# Sheet1.net
KiCad netlist of a schematic drawn in Altium Designer
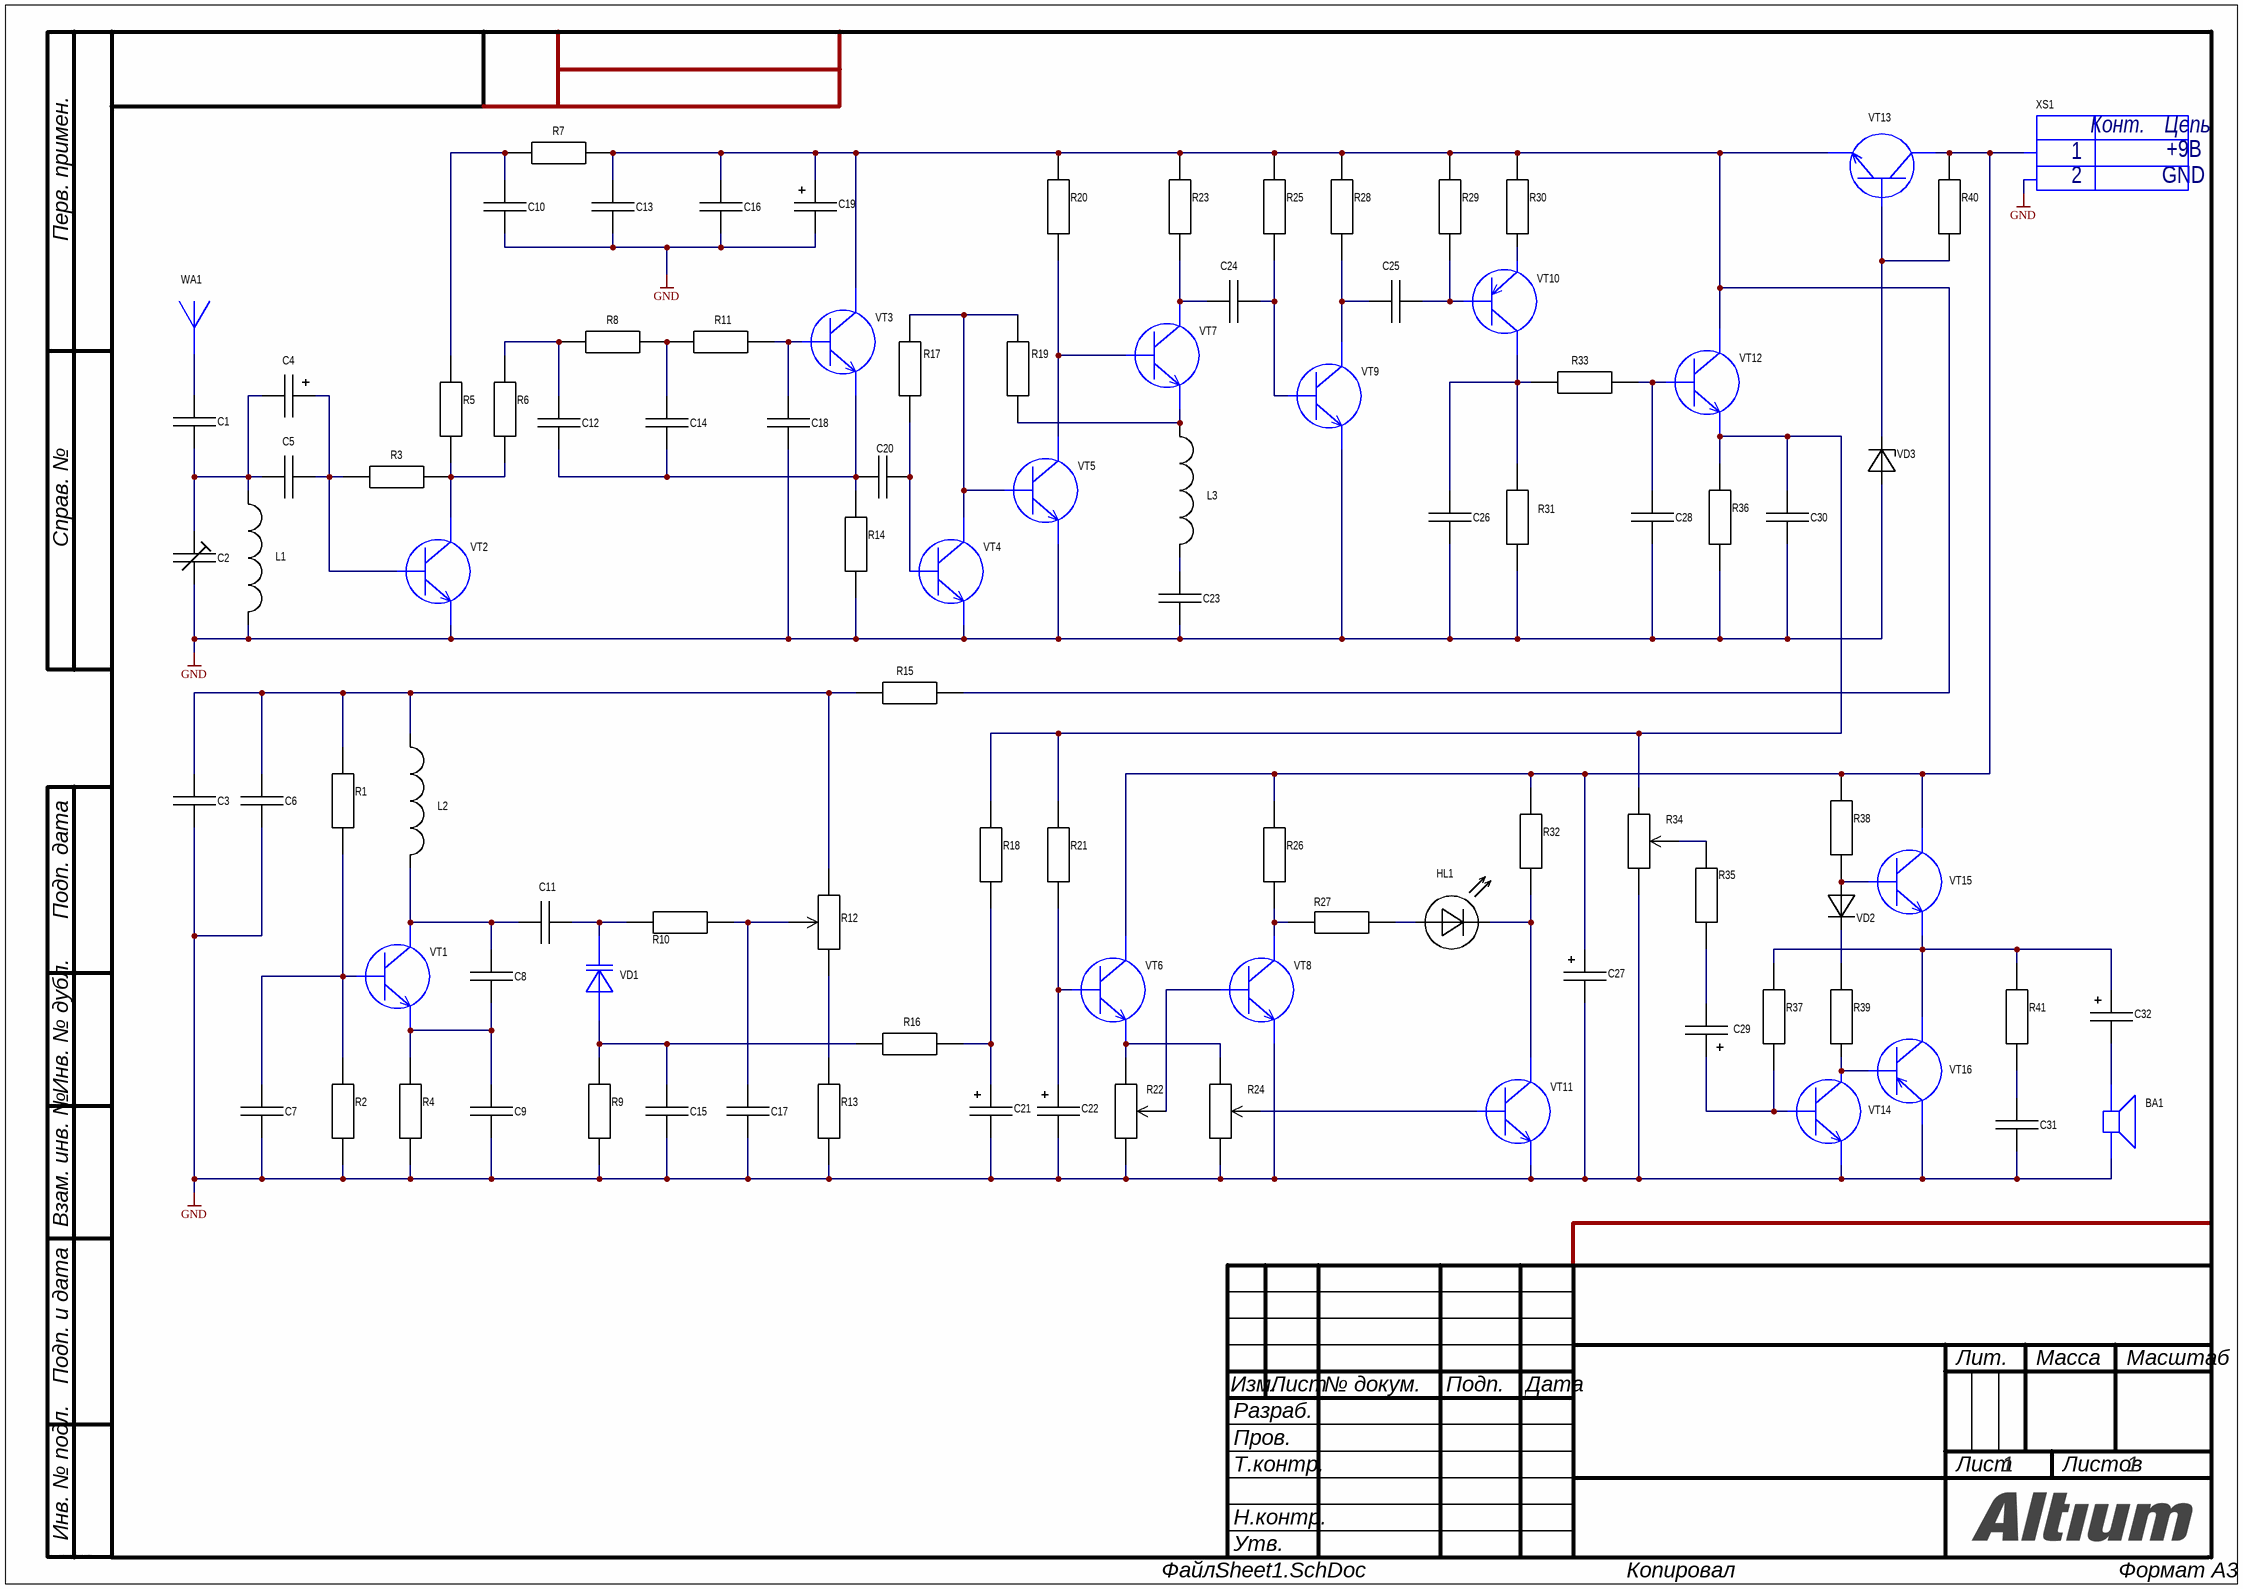
[diagram p0: Sheet1.SchDoc]

(export (version "E")
  (design (tool "Eeschema 10.0.6"))
  (components
    (comp (ref "BA1") (value "speaker") (libsource (lib "AD_lib_GOST") (part "speaker")))
    (comp (ref "C1") (value "15pF") (footprint "CAP-0805") (libsource (lib "AD_lib_GOST") (part "Cap")))
    (comp (ref "C2")
      (value "Cap_rated")
      (footprint "CAP-RATED")
      (libsource (lib "AD_lib_GOST") (part "Cap_rated"))
    )
    (comp (ref "C3") (value "100nF") (footprint "CAP-0805") (libsource (lib "AD_lib_GOST") (part "Cap")))
    (comp (ref "C4")
      (value "10uF")
      (footprint "CAP-SMD-A")
      (libsource (lib "AD_lib_GOST") (part "Cap_polar"))
    )
    (comp (ref "C5") (value "100nF") (footprint "CAP-0805") (libsource (lib "AD_lib_GOST") (part "Cap")))
    (comp (ref "C6") (value "100nF") (footprint "CAP-0805") (libsource (lib "AD_lib_GOST") (part "Cap")))
    (comp (ref "C7") (value "10nF") (footprint "CAP-0805") (libsource (lib "AD_lib_GOST") (part "Cap")))
    (comp (ref "C8") (value "8pF") (footprint "CAP-0805") (libsource (lib "AD_lib_GOST") (part "Cap")))
    (comp (ref "C9") (value "47pF") (footprint "CAP-0805") (libsource (lib "AD_lib_GOST") (part "Cap")))
    (comp (ref "C10") (value "100nF") (footprint "CAP-0805") (libsource (lib "AD_lib_GOST") (part "Cap")))
    (comp (ref "C11") (value "1nF") (footprint "CAP-0805") (libsource (lib "AD_lib_GOST") (part "Cap")))
    (comp (ref "C12") (value "47pF") (footprint "CAP-0805") (libsource (lib "AD_lib_GOST") (part "Cap")))
    (comp (ref "C13") (value "100nF") (footprint "CAP-0805") (libsource (lib "AD_lib_GOST") (part "Cap")))
    (comp (ref "C14") (value "47pF") (footprint "CAP-0805") (libsource (lib "AD_lib_GOST") (part "Cap")))
    (comp (ref "C15") (value "100nF") (footprint "CAP-0805") (libsource (lib "AD_lib_GOST") (part "Cap")))
    (comp (ref "C16") (value "100nF") (footprint "CAP-0805") (libsource (lib "AD_lib_GOST") (part "Cap")))
    (comp (ref "C17") (value "100nF") (footprint "CAP-0805") (libsource (lib "AD_lib_GOST") (part "Cap")))
    (comp (ref "C18") (value "47pF") (footprint "CAP-0805") (libsource (lib "AD_lib_GOST") (part "Cap")))
    (comp (ref "C19")
      (value "220uF")
      (footprint "CAP-SMD-A")
      (libsource (lib "AD_lib_GOST") (part "Cap_polar"))
    )
    (comp (ref "C20") (value "5.1nF") (footprint "CAP-0805") (libsource (lib "AD_lib_GOST") (part "Cap")))
    (comp (ref "C21")
      (value "10uF")
      (footprint "CAP-SMD-A")
      (libsource (lib "AD_lib_GOST") (part "Cap_polar"))
    )
    (comp (ref "C22")
      (value "10uF")
      (footprint "CAP-SMD-A")
      (libsource (lib "AD_lib_GOST") (part "Cap_polar"))
    )
    (comp (ref "C23") (value "15nF") (footprint "CAP-0805") (libsource (lib "AD_lib_GOST") (part "Cap")))
    (comp (ref "C24") (value "22nF") (footprint "CAP-0805") (libsource (lib "AD_lib_GOST") (part "Cap")))
    (comp (ref "C25") (value "39pF") (footprint "CAP-0805") (libsource (lib "AD_lib_GOST") (part "Cap")))
    (comp (ref "C26") (value "1nF") (footprint "CAP-0805") (libsource (lib "AD_lib_GOST") (part "Cap")))
    (comp (ref "C27")
      (value "220uF")
      (footprint "CAP-SMD-A")
      (libsource (lib "AD_lib_GOST") (part "Cap_polar"))
    )
    (comp (ref "C28") (value "3.3nF") (footprint "CAP-0805") (libsource (lib "AD_lib_GOST") (part "Cap")))
    (comp (ref "C29")
      (value "10uF")
      (footprint "CAP-SMD-A")
      (libsource (lib "AD_lib_GOST") (part "Cap_polar"))
    )
    (comp (ref "C30") (value "3.3nF") (footprint "CAP-0805") (libsource (lib "AD_lib_GOST") (part "Cap")))
    (comp (ref "C31") (value "100nF") (footprint "CAP-0805") (libsource (lib "AD_lib_GOST") (part "Cap")))
    (comp (ref "C32")
      (value "220uF")
      (footprint "CAP-SMD-A")
      (libsource (lib "AD_lib_GOST") (part "Cap_polar"))
    )
    (comp (ref "HL1")
      (value "LED white")
      (footprint "LED_RED_5MM")
      (libsource (lib "AD_lib_GOST") (part "Led_1"))
    )
    (comp (ref "L1")
      (value "Inductor coil")
      (footprint "INDUCTOR-AXIS")
      (libsource (lib "AD_lib_GOST") (part "Inductor coil"))
    )
    (comp (ref "L2")
      (value "Inductor coil")
      (footprint "INDUCTOR-AXIS")
      (libsource (lib "AD_lib_GOST") (part "Inductor coil"))
    )
    (comp (ref "L3")
      (value "Inductor coil")
      (footprint "INDUCTOR-AXIS")
      (libsource (lib "AD_lib_GOST") (part "Inductor coil"))
    )
    (comp (ref "R1") (value "15k") (footprint "RES-0805") (libsource (lib "AD_lib_GOST") (part "resistor")))
    (comp (ref "R2") (value "5.1k") (footprint "RES-0805") (libsource (lib "AD_lib_GOST") (part "resistor")))
    (comp (ref "R3") (value "220k") (footprint "RES-0805") (libsource (lib "AD_lib_GOST") (part "resistor")))
    (comp (ref "R4") (value "470") (footprint "RES-0805") (libsource (lib "AD_lib_GOST") (part "resistor")))
    (comp (ref "R5") (value "2k") (footprint "RES-0805") (libsource (lib "AD_lib_GOST") (part "resistor")))
    (comp (ref "R6") (value "6.8k") (footprint "RES-0805") (libsource (lib "AD_lib_GOST") (part "resistor")))
    (comp (ref "R7") (value "1k") (footprint "RES-0805") (libsource (lib "AD_lib_GOST") (part "resistor")))
    (comp (ref "R8") (value "6.8k") (footprint "RES-0805") (libsource (lib "AD_lib_GOST") (part "resistor")))
    (comp (ref "R9") (value "8.2k") (footprint "RES-0805") (libsource (lib "AD_lib_GOST") (part "resistor")))
    (comp (ref "R10") (value "100k") (footprint "RES-0805") (libsource (lib "AD_lib_GOST") (part "resistor")))
    (comp (ref "R11") (value "6.8k") (footprint "RES-0805") (libsource (lib "AD_lib_GOST") (part "resistor")))
    (comp (ref "R12") (value "22k") (footprint "RES-POT-3296W") (libsource (lib "AD_lib_GOST") (part "POT")))
    (comp (ref "R13") (value "1k") (footprint "RES-0805") (libsource (lib "AD_lib_GOST") (part "resistor")))
    (comp (ref "R14") (value "3.3k") (footprint "RES-0805") (libsource (lib "AD_lib_GOST") (part "resistor")))
    (comp (ref "R15") (value "150") (footprint "RES-0805") (libsource (lib "AD_lib_GOST") (part "resistor")))
    (comp (ref "R16") (value "51k") (footprint "RES-0805") (libsource (lib "AD_lib_GOST") (part "resistor")))
    (comp (ref "R17") (value "1.5k") (footprint "RES-0805") (libsource (lib "AD_lib_GOST") (part "resistor")))
    (comp (ref "R18") (value "100k") (footprint "RES-0805") (libsource (lib "AD_lib_GOST") (part "resistor")))
    (comp (ref "R19") (value "2k") (footprint "RES-0805") (libsource (lib "AD_lib_GOST") (part "resistor")))
    (comp (ref "R20") (value "6.8k") (footprint "RES-0805") (libsource (lib "AD_lib_GOST") (part "resistor")))
    (comp (ref "R21") (value "100k") (footprint "RES-0805") (libsource (lib "AD_lib_GOST") (part "resistor")))
    (comp (ref "R22") (value "6.8k") (footprint "RES-POT-3") (libsource (lib "AD_lib_GOST") (part "POT")))
    (comp (ref "R23") (value "1.8k") (footprint "RES-0805") (libsource (lib "AD_lib_GOST") (part "resistor")))
    (comp (ref "R24") (value "6.8k") (footprint "RES-POT-3") (libsource (lib "AD_lib_GOST") (part "POT")))
    (comp (ref "R25") (value "51k") (footprint "RES-0805") (libsource (lib "AD_lib_GOST") (part "resistor")))
    (comp (ref "R26") (value "4.7k") (footprint "RES-0805") (libsource (lib "AD_lib_GOST") (part "resistor")))
    (comp (ref "R27") (value "1k") (footprint "RES-0805") (libsource (lib "AD_lib_GOST") (part "resistor")))
    (comp (ref "R28") (value "4.7k") (footprint "RES-0805") (libsource (lib "AD_lib_GOST") (part "resistor")))
    (comp (ref "R29") (value "4.7k") (footprint "RES-0805") (libsource (lib "AD_lib_GOST") (part "resistor")))
    (comp (ref "R30") (value "220") (footprint "RES-0805") (libsource (lib "AD_lib_GOST") (part "resistor")))
    (comp (ref "R31") (value "8.2k") (footprint "RES-0805") (libsource (lib "AD_lib_GOST") (part "resistor")))
    (comp (ref "R32") (value "4.7k") (footprint "RES-0805") (libsource (lib "AD_lib_GOST") (part "resistor")))
    (comp (ref "R33") (value "18k") (footprint "RES-0805") (libsource (lib "AD_lib_GOST") (part "resistor")))
    (comp (ref "R34") (value "10k") (footprint "RES-POT-2") (libsource (lib "AD_lib_GOST") (part "POT")))
    (comp (ref "R35") (value "4.7k") (footprint "RES-0805") (libsource (lib "AD_lib_GOST") (part "resistor")))
    (comp (ref "R36") (value "3k") (footprint "RES-0805") (libsource (lib "AD_lib_GOST") (part "resistor")))
    (comp (ref "R37") (value "150k") (footprint "RES-0805") (libsource (lib "AD_lib_GOST") (part "resistor")))
    (comp (ref "R38") (value "750") (footprint "RES-0805") (libsource (lib "AD_lib_GOST") (part "resistor")))
    (comp (ref "R39") (value "47") (footprint "RES-0805") (libsource (lib "AD_lib_GOST") (part "resistor")))
    (comp (ref "R40")
      (value "HrenzZnaet(470)")
      (footprint "RES-0805")
      (libsource (lib "AD_lib_GOST") (part "resistor"))
    )
    (comp (ref "R41") (value "10") (footprint "RES-0805") (libsource (lib "AD_lib_GOST") (part "resistor")))
    (comp (ref "VD1") (value "didoe") (footprint "DIODE-AXIS") (libsource (lib "AD_lib_GOST") (part "didoe")))
    (comp (ref "VD2") (value "1N4148W") (footprint "SOD-123") (libsource (lib "AD_lib_GOST") (part "Diode")))
    (comp (ref "VD3")
      (value "BZV55C6V8")
      (footprint "DIODE-MELF")
      (libsource (lib "AD_lib_GOST") (part "Diode_stab"))
    )
    (comp (ref "VT1") (value "SS9018") (footprint "SOT-23-3") (libsource (lib "AD_lib_GOST") (part "NPN_1")))
    (comp (ref "VT2") (value "SS9018") (footprint "SOT-23-3") (libsource (lib "AD_lib_GOST") (part "NPN_1")))
    (comp (ref "VT3") (value "ВС847") (footprint "SOT-23-3") (libsource (lib "AD_lib_GOST") (part "NPN_1")))
    (comp (ref "VT4") (value "ВС847") (footprint "SOT-23-3") (libsource (lib "AD_lib_GOST") (part "NPN_1")))
    (comp (ref "VT5") (value "ВС847") (footprint "SOT-23-3") (libsource (lib "AD_lib_GOST") (part "NPN_1")))
    (comp (ref "VT6") (value "ВС847") (footprint "SOT-23-3") (libsource (lib "AD_lib_GOST") (part "NPN_1")))
    (comp (ref "VT7") (value "ВС847") (footprint "SOT-23-3") (libsource (lib "AD_lib_GOST") (part "NPN_1")))
    (comp (ref "VT8") (value "ВС847") (footprint "SOT-23-3") (libsource (lib "AD_lib_GOST") (part "NPN_1")))
    (comp (ref "VT9") (value "ВС847") (footprint "SOT-23-3") (libsource (lib "AD_lib_GOST") (part "NPN_1")))
    (comp (ref "VT10") (value "BC857") (footprint "SOT-23-3") (libsource (lib "AD_lib_GOST") (part "PNP_1")))
    (comp (ref "VT11") (value "ВС847") (footprint "SOT-23-3") (libsource (lib "AD_lib_GOST") (part "NPN_1")))
    (comp (ref "VT12") (value "ВС847") (footprint "SOT-23-3") (libsource (lib "AD_lib_GOST") (part "NPN_1")))
    (comp (ref "VT13") (value "ВС847") (footprint "SOT-23-3") (libsource (lib "AD_lib_GOST") (part "NPN_1")))
    (comp (ref "VT14") (value "ВС847") (footprint "SOT-23-3") (libsource (lib "AD_lib_GOST") (part "NPN_1")))
    (comp (ref "VT15") (value "BCP56") (footprint "SOT-223") (libsource (lib "AD_lib_GOST") (part "NPN_2")))
    (comp (ref "VT16") (value "BCP53") (footprint "SOT-223") (libsource (lib "AD_lib_GOST") (part "PNP_2")))
    (comp (ref "WA1") (value "Antenna") (libsource (lib "AD_lib_GOST") (part "Antenna")))
    (comp (ref "XS1")
      (value "Connection2")
      (footprint "Power socket")
      (libsource (lib "AD_lib_GOST") (part "Connection2"))
    )
  )
  (nets
    (net (code "1") (name "GND") (class "Default")
      (node (ref "BA1") (pin "1") (pinfunction "1_1") (pintype "passive"))
      (node (ref "C10") (pin "1") (pinfunction "1_1") (pintype "passive"))
      (node (ref "C13") (pin "1") (pinfunction "1_1") (pintype "passive"))
      (node (ref "C15") (pin "1") (pinfunction "1_1") (pintype "passive"))
      (node (ref "C16") (pin "1") (pinfunction "1_1") (pintype "passive"))
      (node (ref "C17") (pin "1") (pinfunction "1_1") (pintype "passive"))
      (node (ref "C18") (pin "1") (pinfunction "1_1") (pintype "passive"))
      (node (ref "C19") (pin "C") (pinfunction "2_C") (pintype "passive"))
      (node (ref "C2") (pin "1") (pinfunction "1_1") (pintype "passive"))
      (node (ref "C21") (pin "C") (pinfunction "2_C") (pintype "passive"))
      (node (ref "C22") (pin "C") (pinfunction "2_C") (pintype "passive"))
      (node (ref "C23") (pin "2") (pinfunction "2_2") (pintype "passive"))
      (node (ref "C26") (pin "2") (pinfunction "2_2") (pintype "passive"))
      (node (ref "C27") (pin "C") (pinfunction "2_C") (pintype "passive"))
      (node (ref "C28") (pin "2") (pinfunction "2_2") (pintype "passive"))
      (node (ref "C3") (pin "1") (pinfunction "1_1") (pintype "passive"))
      (node (ref "C30") (pin "2") (pinfunction "2_2") (pintype "passive"))
      (node (ref "C31") (pin "2") (pinfunction "2_2") (pintype "passive"))
      (node (ref "C6") (pin "1") (pinfunction "1_1") (pintype "passive"))
      (node (ref "C7") (pin "1") (pinfunction "1_1") (pintype "passive"))
      (node (ref "C9") (pin "1") (pinfunction "1_1") (pintype "passive"))
      (node (ref "L1") (pin "2") (pinfunction "2_2") (pintype "passive"))
      (node (ref "R13") (pin "1") (pinfunction "1_1") (pintype "passive"))
      (node (ref "R14") (pin "1") (pinfunction "1_1") (pintype "passive"))
      (node (ref "R2") (pin "2") (pinfunction "2_2") (pintype "passive"))
      (node (ref "R22") (pin "2") (pinfunction "2_2") (pintype "passive"))
      (node (ref "R24") (pin "2") (pinfunction "2_2") (pintype "passive"))
      (node (ref "R31") (pin "2") (pinfunction "2_2") (pintype "passive"))
      (node (ref "R34") (pin "2") (pinfunction "2_2") (pintype "passive"))
      (node (ref "R36") (pin "2") (pinfunction "2_2") (pintype "passive"))
      (node (ref "R4") (pin "2") (pinfunction "2_2") (pintype "passive"))
      (node (ref "R9") (pin "2") (pinfunction "2_2") (pintype "passive"))
      (node (ref "VD3") (pin "A") (pinfunction "1_A") (pintype "passive"))
      (node (ref "VT11") (pin "2") (pinfunction "Э_2") (pintype "passive"))
      (node (ref "VT14") (pin "2") (pinfunction "Э_2") (pintype "passive"))
      (node (ref "VT16") (pin "3") (pinfunction "Э_3") (pintype "passive"))
      (node (ref "VT2") (pin "2") (pinfunction "Э_2") (pintype "passive"))
      (node (ref "VT4") (pin "2") (pinfunction "Э_2") (pintype "passive"))
      (node (ref "VT5") (pin "2") (pinfunction "Э_2") (pintype "passive"))
      (node (ref "VT8") (pin "2") (pinfunction "Э_2") (pintype "passive"))
      (node (ref "VT9") (pin "2") (pinfunction "Э_2") (pintype "passive"))
      (node (ref "XS1") (pin "G") (pinfunction "2_G") (pintype "passive"))
    )
    (net (code "2") (name "Net-(C1-Pad1)") (class "Default")
      (node (ref "C1") (pin "1") (pinfunction "1_1") (pintype "passive"))
      (node (ref "WA1") (pin "1") (pinfunction "1_1") (pintype "passive"))
    )
    (net (code "3") (name "Net-(C3-Pad2)") (class "Default")
      (node (ref "C3") (pin "2") (pinfunction "2_2") (pintype "passive"))
      (node (ref "C6") (pin "2") (pinfunction "2_2") (pintype "passive"))
      (node (ref "L2") (pin "1") (pinfunction "1_1") (pintype "passive"))
      (node (ref "R1") (pin "1") (pinfunction "1_1") (pintype "passive"))
      (node (ref "R12") (pin "2") (pinfunction "2_2") (pintype "passive"))
      (node (ref "R15") (pin "2") (pinfunction "2_2") (pintype "passive"))
    )
    (net (code "4") (name "Net-(C4-1)") (class "Default")
      (node (ref "C4") (pin "A") (pinfunction "1_A") (pintype "passive"))
      (node (ref "C5") (pin "2") (pinfunction "2_2") (pintype "passive"))
      (node (ref "R3") (pin "2") (pinfunction "2_2") (pintype "passive"))
      (node (ref "VT2") (pin "1") (pinfunction "Б_1") (pintype "passive"))
    )
    (net (code "5") (name "Net-(C4-2)") (class "Default")
      (node (ref "C1") (pin "2") (pinfunction "2_2") (pintype "passive"))
      (node (ref "C2") (pin "2") (pinfunction "2_2") (pintype "passive"))
      (node (ref "C4") (pin "C") (pinfunction "2_C") (pintype "passive"))
      (node (ref "C5") (pin "1") (pinfunction "1_1") (pintype "passive"))
      (node (ref "L1") (pin "1") (pinfunction "1_1") (pintype "passive"))
    )
    (net (code "6") (name "Net-(C10-Pad2)") (class "Default")
      (node (ref "C10") (pin "2") (pinfunction "2_2") (pintype "passive"))
      (node (ref "R5") (pin "2") (pinfunction "2_2") (pintype "passive"))
      (node (ref "R7") (pin "1") (pinfunction "1_1") (pintype "passive"))
    )
    (net (code "7") (name "Net-(C12-Pad2)") (class "Default")
      (node (ref "C12") (pin "2") (pinfunction "2_2") (pintype "passive"))
      (node (ref "R6") (pin "1") (pinfunction "1_1") (pintype "passive"))
      (node (ref "R8") (pin "2") (pinfunction "2_2") (pintype "passive"))
    )
    (net (code "8") (name "Net-(C14-Pad2)") (class "Default")
      (node (ref "C14") (pin "2") (pinfunction "2_2") (pintype "passive"))
      (node (ref "R11") (pin "1") (pinfunction "1_1") (pintype "passive"))
      (node (ref "R8") (pin "1") (pinfunction "1_1") (pintype "passive"))
    )
    (net (code "9") (name "Net-(C17-Pad2)") (class "Default")
      (node (ref "C17") (pin "2") (pinfunction "2_2") (pintype "passive"))
      (node (ref "R10") (pin "2") (pinfunction "2_2") (pintype "passive"))
      (node (ref "R12") (pin "3") (pinfunction "3_3") (pintype "passive"))
    )
    (net (code "10") (name "Net-(C19-1)") (class "Default")
      (node (ref "C13") (pin "2") (pinfunction "2_2") (pintype "passive"))
      (node (ref "C16") (pin "2") (pinfunction "2_2") (pintype "passive"))
      (node (ref "C19") (pin "A") (pinfunction "1_A") (pintype "passive"))
      (node (ref "R15") (pin "1") (pinfunction "1_1") (pintype "passive"))
      (node (ref "R20") (pin "1") (pinfunction "1_1") (pintype "passive"))
      (node (ref "R23") (pin "1") (pinfunction "1_1") (pintype "passive"))
      (node (ref "R25") (pin "1") (pinfunction "1_1") (pintype "passive"))
      (node (ref "R28") (pin "1") (pinfunction "1_1") (pintype "passive"))
      (node (ref "R29") (pin "1") (pinfunction "1_1") (pintype "passive"))
      (node (ref "R30") (pin "1") (pinfunction "1_1") (pintype "passive"))
      (node (ref "R7") (pin "2") (pinfunction "2_2") (pintype "passive"))
      (node (ref "VT12") (pin "3") (pinfunction "К_3") (pintype "passive"))
      (node (ref "VT13") (pin "2") (pinfunction "Э_2") (pintype "passive"))
      (node (ref "VT3") (pin "3") (pinfunction "К_3") (pintype "passive"))
    )
    (net (code "11") (name "Net-(C21-1)") (class "Default")
      (node (ref "C21") (pin "A") (pinfunction "1_A") (pintype "passive"))
      (node (ref "R16") (pin "1") (pinfunction "1_1") (pintype "passive"))
      (node (ref "R18") (pin "2") (pinfunction "2_2") (pintype "passive"))
    )
    (net (code "12") (name "Net-(C22-1)") (class "Default")
      (node (ref "C22") (pin "A") (pinfunction "1_A") (pintype "passive"))
      (node (ref "R21") (pin "2") (pinfunction "2_2") (pintype "passive"))
      (node (ref "VT6") (pin "1") (pinfunction "Б_1") (pintype "passive"))
    )
    (net (code "13") (name "Net-(C23-Pad1)") (class "Default")
      (node (ref "C23") (pin "1") (pinfunction "1_1") (pintype "passive"))
      (node (ref "L3") (pin "2") (pinfunction "2_2") (pintype "passive"))
    )
    (net (code "14") (name "Net-(C27-1)") (class "Default")
      (node (ref "C27") (pin "A") (pinfunction "1_A") (pintype "passive"))
      (node (ref "R26") (pin "1") (pinfunction "1_1") (pintype "passive"))
      (node (ref "R32") (pin "1") (pinfunction "1_1") (pintype "passive"))
      (node (ref "R38") (pin "2") (pinfunction "2_2") (pintype "passive"))
      (node (ref "R40") (pin "1") (pinfunction "1_1") (pintype "passive"))
      (node (ref "VT13") (pin "3") (pinfunction "К_3") (pintype "passive"))
      (node (ref "VT15") (pin "2") (pinfunction "К_2") (pintype "passive"))
      (node (ref "VT6") (pin "3") (pinfunction "К_3") (pintype "passive"))
      (node (ref "XS1") (pin "V") (pinfunction "1_V") (pintype "passive"))
    )
    (net (code "15") (name "Net-(C29-1)") (class "Default")
      (node (ref "C29") (pin "A") (pinfunction "1_A") (pintype "passive"))
      (node (ref "R37") (pin "2") (pinfunction "2_2") (pintype "passive"))
      (node (ref "VT14") (pin "1") (pinfunction "Б_1") (pintype "passive"))
    )
    (net (code "16") (name "Net-(C29-2)") (class "Default")
      (node (ref "C29") (pin "C") (pinfunction "2_C") (pintype "passive"))
      (node (ref "R35") (pin "1") (pinfunction "1_1") (pintype "passive"))
    )
    (net (code "17") (name "Net-(C31-Pad1)") (class "Default")
      (node (ref "C31") (pin "1") (pinfunction "1_1") (pintype "passive"))
      (node (ref "R41") (pin "1") (pinfunction "1_1") (pintype "passive"))
    )
    (net (code "18") (name "Net-(C32-1)") (class "Default")
      (node (ref "C32") (pin "A") (pinfunction "1_A") (pintype "passive"))
      (node (ref "R37") (pin "1") (pinfunction "1_1") (pintype "passive"))
      (node (ref "R41") (pin "2") (pinfunction "2_2") (pintype "passive"))
      (node (ref "VT15") (pin "3") (pinfunction "Э_3") (pintype "passive"))
      (node (ref "VT16") (pin "2") (pinfunction "К_2") (pintype "passive"))
    )
    (net (code "19") (name "Net-(C32-2)") (class "Default")
      (node (ref "BA1") (pin "0") (pinfunction "0_0") (pintype "passive"))
      (node (ref "C32") (pin "C") (pinfunction "2_C") (pintype "passive"))
    )
    (net (code "20") (name "Net-(HL1-Pad1)") (class "Default")
      (node (ref "HL1") (pin "1") (pinfunction "1_1") (pintype "passive"))
      (node (ref "R27") (pin "2") (pinfunction "2_2") (pintype "passive"))
    )
    (net (code "21") (name "Net-(R12-Pad1)") (class "Default")
      (node (ref "R12") (pin "1") (pinfunction "1_1") (pintype "passive"))
      (node (ref "R13") (pin "2") (pinfunction "2_2") (pintype "passive"))
    )
    (net (code "22") (name "Net-(R34-Pad3)") (class "Default")
      (node (ref "R34") (pin "3") (pinfunction "3_3") (pintype "passive"))
      (node (ref "R35") (pin "2") (pinfunction "2_2") (pintype "passive"))
    )
    (net (code "23") (name "Net-(VD1-А)") (class "Default")
      (node (ref "C15") (pin "2") (pinfunction "2_2") (pintype "passive"))
      (node (ref "R16") (pin "2") (pinfunction "2_2") (pintype "passive"))
      (node (ref "R9") (pin "1") (pinfunction "1_1") (pintype "passive"))
      (node (ref "VD1") (pin "A") (pinfunction "А_A") (pintype "passive"))
    )
    (net (code "24") (name "Net-(VD1-К)") (class "Default")
      (node (ref "C11") (pin "1") (pinfunction "1_1") (pintype "passive"))
      (node (ref "R10") (pin "1") (pinfunction "1_1") (pintype "passive"))
      (node (ref "VD1") (pin "C") (pinfunction "К_C") (pintype "passive"))
    )
    (net (code "25") (name "Net-(VD2-1)") (class "Default")
      (node (ref "R38") (pin "1") (pinfunction "1_1") (pintype "passive"))
      (node (ref "VD2") (pin "A") (pinfunction "1_A") (pintype "passive"))
      (node (ref "VT15") (pin "1") (pinfunction "Б_1") (pintype "passive"))
    )
    (net (code "26") (name "Net-(VD2-2)") (class "Default")
      (node (ref "R39") (pin "2") (pinfunction "2_2") (pintype "passive"))
      (node (ref "VD2") (pin "C") (pinfunction "2_C") (pintype "passive"))
    )
    (net (code "27") (name "Net-(VD3-2)") (class "Default")
      (node (ref "R40") (pin "2") (pinfunction "2_2") (pintype "passive"))
      (node (ref "VD3") (pin "C") (pinfunction "2_C") (pintype "passive"))
      (node (ref "VT13") (pin "1") (pinfunction "Б_1") (pintype "passive"))
    )
    (net (code "28") (name "Net-(VT1-Б)") (class "Default")
      (node (ref "C7") (pin "2") (pinfunction "2_2") (pintype "passive"))
      (node (ref "R1") (pin "2") (pinfunction "2_2") (pintype "passive"))
      (node (ref "R2") (pin "1") (pinfunction "1_1") (pintype "passive"))
      (node (ref "VT1") (pin "1") (pinfunction "Б_1") (pintype "passive"))
    )
    (net (code "29") (name "Net-(VT1-К)") (class "Default")
      (node (ref "C11") (pin "2") (pinfunction "2_2") (pintype "passive"))
      (node (ref "C8") (pin "2") (pinfunction "2_2") (pintype "passive"))
      (node (ref "L2") (pin "2") (pinfunction "2_2") (pintype "passive"))
      (node (ref "VT1") (pin "3") (pinfunction "К_3") (pintype "passive"))
    )
    (net (code "30") (name "Net-(VT1-Э)") (class "Default")
      (node (ref "C8") (pin "1") (pinfunction "1_1") (pintype "passive"))
      (node (ref "C9") (pin "2") (pinfunction "2_2") (pintype "passive"))
      (node (ref "R4") (pin "1") (pinfunction "1_1") (pintype "passive"))
      (node (ref "VT1") (pin "2") (pinfunction "Э_2") (pintype "passive"))
    )
    (net (code "31") (name "Net-(VT2-К)") (class "Default")
      (node (ref "R3") (pin "1") (pinfunction "1_1") (pintype "passive"))
      (node (ref "R5") (pin "1") (pinfunction "1_1") (pintype "passive"))
      (node (ref "R6") (pin "2") (pinfunction "2_2") (pintype "passive"))
      (node (ref "VT2") (pin "3") (pinfunction "К_3") (pintype "passive"))
    )
    (net (code "32") (name "Net-(VT3-Б)") (class "Default")
      (node (ref "C18") (pin "2") (pinfunction "2_2") (pintype "passive"))
      (node (ref "R11") (pin "2") (pinfunction "2_2") (pintype "passive"))
      (node (ref "VT3") (pin "1") (pinfunction "Б_1") (pintype "passive"))
    )
    (net (code "33") (name "Net-(VT3-Э)") (class "Default")
      (node (ref "C12") (pin "1") (pinfunction "1_1") (pintype "passive"))
      (node (ref "C14") (pin "1") (pinfunction "1_1") (pintype "passive"))
      (node (ref "C20") (pin "2") (pinfunction "2_2") (pintype "passive"))
      (node (ref "R14") (pin "2") (pinfunction "2_2") (pintype "passive"))
      (node (ref "VT3") (pin "2") (pinfunction "Э_2") (pintype "passive"))
    )
    (net (code "34") (name "Net-(VT4-Б)") (class "Default")
      (node (ref "C20") (pin "1") (pinfunction "1_1") (pintype "passive"))
      (node (ref "R17") (pin "1") (pinfunction "1_1") (pintype "passive"))
      (node (ref "VT4") (pin "1") (pinfunction "Б_1") (pintype "passive"))
    )
    (net (code "35") (name "Net-(VT4-К)") (class "Default")
      (node (ref "R17") (pin "2") (pinfunction "2_2") (pintype "passive"))
      (node (ref "R19") (pin "1") (pinfunction "1_1") (pintype "passive"))
      (node (ref "VT4") (pin "3") (pinfunction "К_3") (pintype "passive"))
      (node (ref "VT5") (pin "1") (pinfunction "Б_1") (pintype "passive"))
    )
    (net (code "36") (name "Net-(VT5-К)") (class "Default")
      (node (ref "R20") (pin "2") (pinfunction "2_2") (pintype "passive"))
      (node (ref "VT5") (pin "3") (pinfunction "К_3") (pintype "passive"))
      (node (ref "VT7") (pin "1") (pinfunction "Б_1") (pintype "passive"))
    )
    (net (code "37") (name "Net-(VT6-Э)") (class "Default")
      (node (ref "R22") (pin "1") (pinfunction "1_1") (pintype "passive"))
      (node (ref "R24") (pin "1") (pinfunction "1_1") (pintype "passive"))
      (node (ref "VT6") (pin "2") (pinfunction "Э_2") (pintype "passive"))
    )
    (net (code "38") (name "Net-(VT7-К)") (class "Default")
      (node (ref "C24") (pin "2") (pinfunction "2_2") (pintype "passive"))
      (node (ref "R23") (pin "2") (pinfunction "2_2") (pintype "passive"))
      (node (ref "VT7") (pin "3") (pinfunction "К_3") (pintype "passive"))
    )
    (net (code "39") (name "Net-(VT7-Э)") (class "Default")
      (node (ref "L3") (pin "1") (pinfunction "1_1") (pintype "passive"))
      (node (ref "R19") (pin "2") (pinfunction "2_2") (pintype "passive"))
      (node (ref "VT7") (pin "2") (pinfunction "Э_2") (pintype "passive"))
    )
    (net (code "40") (name "Net-(VT8-Б)") (class "Default")
      (node (ref "R22") (pin "3") (pinfunction "3_3") (pintype "passive"))
      (node (ref "VT8") (pin "1") (pinfunction "Б_1") (pintype "passive"))
    )
    (net (code "41") (name "Net-(VT8-К)") (class "Default")
      (node (ref "R26") (pin "2") (pinfunction "2_2") (pintype "passive"))
      (node (ref "R27") (pin "1") (pinfunction "1_1") (pintype "passive"))
      (node (ref "VT8") (pin "3") (pinfunction "К_3") (pintype "passive"))
    )
    (net (code "42") (name "Net-(VT9-Б)") (class "Default")
      (node (ref "C24") (pin "1") (pinfunction "1_1") (pintype "passive"))
      (node (ref "R25") (pin "2") (pinfunction "2_2") (pintype "passive"))
      (node (ref "VT9") (pin "1") (pinfunction "Б_1") (pintype "passive"))
    )
    (net (code "43") (name "Net-(VT9-К)") (class "Default")
      (node (ref "C25") (pin "2") (pinfunction "2_2") (pintype "passive"))
      (node (ref "R28") (pin "2") (pinfunction "2_2") (pintype "passive"))
      (node (ref "VT9") (pin "3") (pinfunction "К_3") (pintype "passive"))
    )
    (net (code "44") (name "Net-(VT10-Б)") (class "Default")
      (node (ref "C25") (pin "1") (pinfunction "1_1") (pintype "passive"))
      (node (ref "R29") (pin "2") (pinfunction "2_2") (pintype "passive"))
      (node (ref "VT10") (pin "1") (pinfunction "Б_1") (pintype "passive"))
    )
    (net (code "45") (name "Net-(VT10-К)") (class "Default")
      (node (ref "C26") (pin "1") (pinfunction "1_1") (pintype "passive"))
      (node (ref "R31") (pin "1") (pinfunction "1_1") (pintype "passive"))
      (node (ref "R33") (pin "2") (pinfunction "2_2") (pintype "passive"))
      (node (ref "VT10") (pin "3") (pinfunction "К_3") (pintype "passive"))
    )
    (net (code "46") (name "Net-(VT10-Э)") (class "Default")
      (node (ref "R30") (pin "2") (pinfunction "2_2") (pintype "passive"))
      (node (ref "VT10") (pin "2") (pinfunction "Э_2") (pintype "passive"))
    )
    (net (code "47") (name "Net-(VT11-Б)") (class "Default")
      (node (ref "R24") (pin "3") (pinfunction "3_3") (pintype "passive"))
      (node (ref "VT11") (pin "1") (pinfunction "Б_1") (pintype "passive"))
    )
    (net (code "48") (name "Net-(VT11-К)") (class "Default")
      (node (ref "HL1") (pin "2") (pinfunction "2_2") (pintype "passive"))
      (node (ref "R32") (pin "2") (pinfunction "2_2") (pintype "passive"))
      (node (ref "VT11") (pin "3") (pinfunction "К_3") (pintype "passive"))
    )
    (net (code "49") (name "Net-(VT12-Б)") (class "Default")
      (node (ref "C28") (pin "1") (pinfunction "1_1") (pintype "passive"))
      (node (ref "R33") (pin "1") (pinfunction "1_1") (pintype "passive"))
      (node (ref "VT12") (pin "1") (pinfunction "Б_1") (pintype "passive"))
    )
    (net (code "50") (name "Net-(VT12-Э)") (class "Default")
      (node (ref "C30") (pin "1") (pinfunction "1_1") (pintype "passive"))
      (node (ref "R18") (pin "1") (pinfunction "1_1") (pintype "passive"))
      (node (ref "R21") (pin "1") (pinfunction "1_1") (pintype "passive"))
      (node (ref "R34") (pin "1") (pinfunction "1_1") (pintype "passive"))
      (node (ref "R36") (pin "1") (pinfunction "1_1") (pintype "passive"))
      (node (ref "VT12") (pin "2") (pinfunction "Э_2") (pintype "passive"))
    )
    (net (code "51") (name "Net-(VT14-К)") (class "Default")
      (node (ref "R39") (pin "1") (pinfunction "1_1") (pintype "passive"))
      (node (ref "VT14") (pin "3") (pinfunction "К_3") (pintype "passive"))
      (node (ref "VT16") (pin "1") (pinfunction "Б_1") (pintype "passive"))
    )
  )
)
